# apresenta_o1.net
KiCad netlist of a schematic drawn in Altium Designer
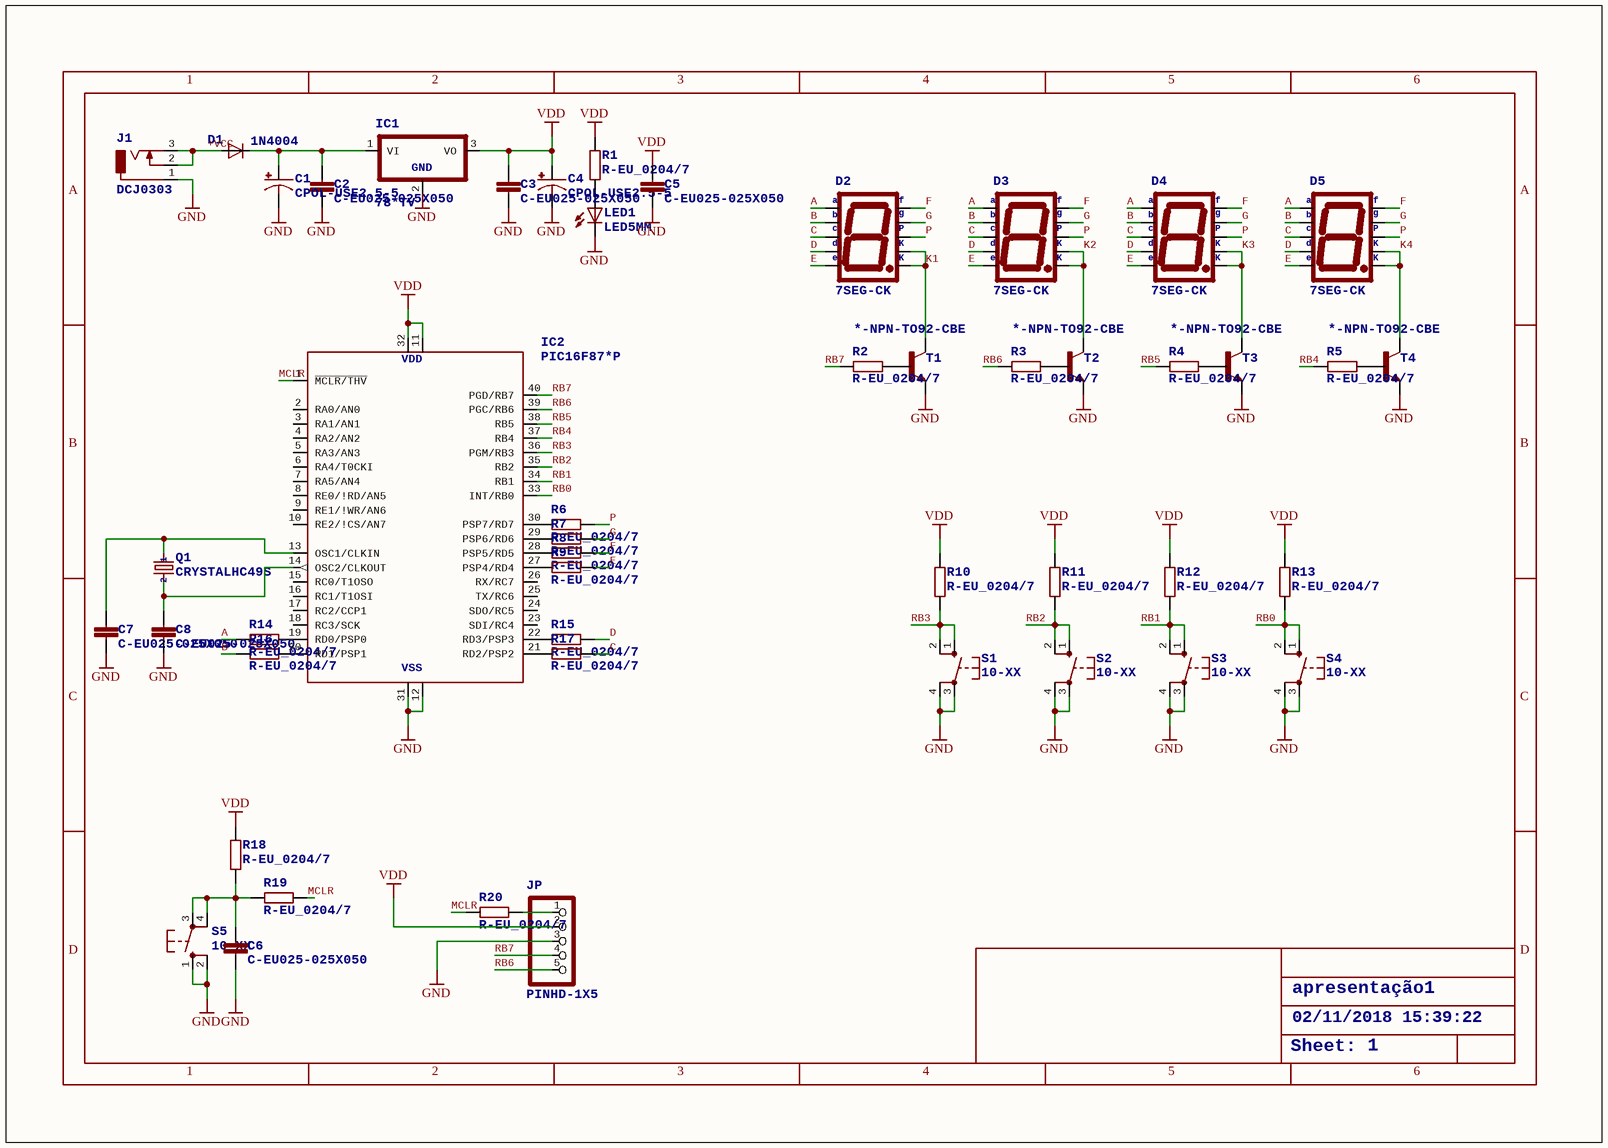
[diagram p0: apresentação1.SchDoc]

(export (version "E")
  (design (tool "Eeschema 10.0.6"))
  (components
    (comp (ref "C1")
      (value "CPOL-USE2.5-5")
      (footprint "E2,5-5")
      (description "POLARIZED CAPACITOR, American symbol")
      (libsource (lib "rcl") (part "CPOL-USE2.5-5"))
    )
    (comp (ref "C2")
      (value "C-EU025-025X050")
      (footprint "C025-025X050")
      (description "CAPACITOR, European symbol")
      (libsource (lib "rcl") (part "C-EU025-025X050"))
    )
    (comp (ref "C3")
      (value "C-EU025-025X050")
      (footprint "C025-025X050")
      (description "CAPACITOR, European symbol")
      (libsource (lib "rcl") (part "C-EU025-025X050"))
    )
    (comp (ref "C4")
      (value "CPOL-USE2.5-5")
      (footprint "E2,5-5")
      (description "POLARIZED CAPACITOR, American symbol")
      (libsource (lib "rcl") (part "CPOL-USE2.5-5"))
    )
    (comp (ref "C5")
      (value "C-EU025-025X050")
      (footprint "C025-025X050")
      (description "CAPACITOR, European symbol")
      (libsource (lib "rcl") (part "C-EU025-025X050"))
    )
    (comp (ref "C6")
      (value "C-EU025-025X050")
      (footprint "C025-025X050")
      (description "CAPACITOR, European symbol")
      (libsource (lib "rcl") (part "C-EU025-025X050"))
    )
    (comp (ref "C7")
      (value "C-EU025-025X050")
      (footprint "C025-025X050")
      (description "CAPACITOR, European symbol")
      (libsource (lib "rcl") (part "C-EU025-025X050"))
    )
    (comp (ref "C8")
      (value "C-EU025-025X050")
      (footprint "C025-025X050")
      (description "CAPACITOR, European symbol")
      (libsource (lib "rcl") (part "C-EU025-025X050"))
    )
    (comp (ref "D1")
      (value "1N4004")
      (footprint "DO41-10")
      (description "DIODE   general purpose rectifier, 1 A")
      (libsource (lib "diode") (part "1N4004"))
    )
    (comp (ref "D2")
      (value "7SEG-CK")
      (footprint "7SEG-13")
      (description "7-segment DISPLAY   single cathode, 13 mm")
      (fields
        (field (name "A") "a")
        (field (name "B") "b")
        (field (name "C") "c")
        (field (name "D") "d")
        (field (name "E") "e")
        (field (name "F") "f")
        (field (name "G") "g")
        (field (name "P") "P")
        (field (name "K") "K")
        (field (name "K_1") "K")
      )
      (libsource (lib "special") (part "7SEG-CK"))
    )
    (comp (ref "D3")
      (value "7SEG-CK")
      (footprint "7SEG-13")
      (description "7-segment DISPLAY   single cathode, 13 mm")
      (fields
        (field (name "A") "a")
        (field (name "B") "b")
        (field (name "C") "c")
        (field (name "D") "d")
        (field (name "E") "e")
        (field (name "F") "f")
        (field (name "G") "g")
        (field (name "P") "P")
        (field (name "K") "K")
        (field (name "K_1") "K")
      )
      (libsource (lib "special") (part "7SEG-CK"))
    )
    (comp (ref "D4")
      (value "7SEG-CK")
      (footprint "7SEG-13")
      (description "7-segment DISPLAY   single cathode, 13 mm")
      (fields
        (field (name "A") "a")
        (field (name "B") "b")
        (field (name "C") "c")
        (field (name "D") "d")
        (field (name "E") "e")
        (field (name "F") "f")
        (field (name "G") "g")
        (field (name "P") "P")
        (field (name "K") "K")
        (field (name "K_1") "K")
      )
      (libsource (lib "special") (part "7SEG-CK"))
    )
    (comp (ref "D5")
      (value "7SEG-CK")
      (footprint "7SEG-13")
      (description "7-segment DISPLAY   single cathode, 13 mm")
      (fields
        (field (name "A") "a")
        (field (name "B") "b")
        (field (name "C") "c")
        (field (name "D") "d")
        (field (name "E") "e")
        (field (name "F") "f")
        (field (name "G") "g")
        (field (name "P") "P")
        (field (name "K") "K")
        (field (name "K_1") "K")
      )
      (libsource (lib "special") (part "7SEG-CK"))
    )
    (comp (ref "IC1")
      (value "78*TV")
      (footprint "TO220V")
      (fields (field (name "GND") "GND"))
      (libsource (lib "linear") (part "78*TV"))
    )
    (comp (ref "IC2")
      (value "PIC16F87*P")
      (footprint "DIL40")
      (description "MICROCONTROLLER")
      (fields
        (field (name "MF") "MICROCHIP")
        (field (name "MPN") "PIC16F874-04I/P")
        (field (name "VDD") "VDD")
        (field (name "VSS") "VSS")
      )
      (libsource (lib "microchip") (part "PIC16F87*P"))
    )
    (comp (ref "J1")
      (value "DCJ0303")
      (footprint "DCJ0303")
      (description "DC POWER JACK   Source: DCJ0303.pdf")
      (libsource (lib "con-jack") (part "DCJ0303"))
    )
    (comp (ref "JP")
      (value "PINHD-1X5")
      (footprint "1X05")
      (description "PIN HEADER")
      (libsource (lib "pinhead") (part "PINHD-1X5"))
    )
    (comp (ref "LED1") (value "LED5MM") (footprint "LED5MM") (libsource (lib "led") (part "LED5MM")))
    (comp (ref "Q1")
      (value "CRYSTALHC49S")
      (footprint "HC49/S")
      (description "CRYSTAL")
      (fields (field (name "1") "1") (field (name "2") "2"))
      (libsource (lib "crystal") (part "CRYSTALHC49S"))
    )
    (comp (ref "R1")
      (value "R-EU_0204/7")
      (footprint "0204/7")
      (description "RESISTOR, European symbol")
      (libsource (lib "rcl") (part "R-EU_0204/7"))
    )
    (comp (ref "R2")
      (value "R-EU_0204/7")
      (footprint "0204/7")
      (description "RESISTOR, European symbol")
      (libsource (lib "rcl") (part "R-EU_0204/7"))
    )
    (comp (ref "R3")
      (value "R-EU_0204/7")
      (footprint "0204/7")
      (description "RESISTOR, European symbol")
      (libsource (lib "rcl") (part "R-EU_0204/7"))
    )
    (comp (ref "R4")
      (value "R-EU_0204/7")
      (footprint "0204/7")
      (description "RESISTOR, European symbol")
      (libsource (lib "rcl") (part "R-EU_0204/7"))
    )
    (comp (ref "R5")
      (value "R-EU_0204/7")
      (footprint "0204/7")
      (description "RESISTOR, European symbol")
      (libsource (lib "rcl") (part "R-EU_0204/7"))
    )
    (comp (ref "R6")
      (value "R-EU_0204/7")
      (footprint "0204/7")
      (description "RESISTOR, European symbol")
      (libsource (lib "rcl") (part "R-EU_0204/7"))
    )
    (comp (ref "R7")
      (value "R-EU_0204/7")
      (footprint "0204/7")
      (description "RESISTOR, European symbol")
      (libsource (lib "rcl") (part "R-EU_0204/7"))
    )
    (comp (ref "R8")
      (value "R-EU_0204/7")
      (footprint "0204/7")
      (description "RESISTOR, European symbol")
      (libsource (lib "rcl") (part "R-EU_0204/7"))
    )
    (comp (ref "R9")
      (value "R-EU_0204/7")
      (footprint "0204/7")
      (description "RESISTOR, European symbol")
      (libsource (lib "rcl") (part "R-EU_0204/7"))
    )
    (comp (ref "R10")
      (value "R-EU_0204/7")
      (footprint "0204/7")
      (description "RESISTOR, European symbol")
      (libsource (lib "rcl") (part "R-EU_0204/7"))
    )
    (comp (ref "R11")
      (value "R-EU_0204/7")
      (footprint "0204/7")
      (description "RESISTOR, European symbol")
      (libsource (lib "rcl") (part "R-EU_0204/7"))
    )
    (comp (ref "R12")
      (value "R-EU_0204/7")
      (footprint "0204/7")
      (description "RESISTOR, European symbol")
      (libsource (lib "rcl") (part "R-EU_0204/7"))
    )
    (comp (ref "R13")
      (value "R-EU_0204/7")
      (footprint "0204/7")
      (description "RESISTOR, European symbol")
      (libsource (lib "rcl") (part "R-EU_0204/7"))
    )
    (comp (ref "R14")
      (value "R-EU_0204/7")
      (footprint "0204/7")
      (description "RESISTOR, European symbol")
      (libsource (lib "rcl") (part "R-EU_0204/7"))
    )
    (comp (ref "R15")
      (value "R-EU_0204/7")
      (footprint "0204/7")
      (description "RESISTOR, European symbol")
      (libsource (lib "rcl") (part "R-EU_0204/7"))
    )
    (comp (ref "R16")
      (value "R-EU_0204/7")
      (footprint "0204/7")
      (description "RESISTOR, European symbol")
      (libsource (lib "rcl") (part "R-EU_0204/7"))
    )
    (comp (ref "R17")
      (value "R-EU_0204/7")
      (footprint "0204/7")
      (description "RESISTOR, European symbol")
      (libsource (lib "rcl") (part "R-EU_0204/7"))
    )
    (comp (ref "R18")
      (value "R-EU_0204/7")
      (footprint "0204/7")
      (description "RESISTOR, European symbol")
      (libsource (lib "rcl") (part "R-EU_0204/7"))
    )
    (comp (ref "R19")
      (value "R-EU_0204/7")
      (footprint "0204/7")
      (description "RESISTOR, European symbol")
      (libsource (lib "rcl") (part "R-EU_0204/7"))
    )
    (comp (ref "R20")
      (value "R-EU_0204/7")
      (footprint "0204/7")
      (description "RESISTOR, European symbol")
      (libsource (lib "rcl") (part "R-EU_0204/7"))
    )
    (comp (ref "S1")
      (value "10-XX")
      (footprint "B3F-10XX")
      (description "OMRON SWITCH")
      (fields (field (name "MPN") "B3F-1000"))
      (libsource (lib "switch-omron") (part "10-XX"))
    )
    (comp (ref "S2")
      (value "10-XX")
      (footprint "B3F-10XX")
      (description "OMRON SWITCH")
      (fields (field (name "MPN") "B3F-1000"))
      (libsource (lib "switch-omron") (part "10-XX"))
    )
    (comp (ref "S3")
      (value "10-XX")
      (footprint "B3F-10XX")
      (description "OMRON SWITCH")
      (fields (field (name "MPN") "B3F-1000"))
      (libsource (lib "switch-omron") (part "10-XX"))
    )
    (comp (ref "S4")
      (value "10-XX")
      (footprint "B3F-10XX")
      (description "OMRON SWITCH")
      (fields (field (name "MPN") "B3F-1000"))
      (libsource (lib "switch-omron") (part "10-XX"))
    )
    (comp (ref "S5")
      (value "10-XX")
      (footprint "B3F-10XX")
      (description "OMRON SWITCH")
      (fields (field (name "MPN") "B3F-1000"))
      (libsource (lib "switch-omron") (part "10-XX"))
    )
    (comp (ref "T1")
      (value "*-NPN-TO92-CBE")
      (footprint "TO92-CBE")
      (description "NPN Transistror   BF959 corrected 2008.03.06")
      (libsource (lib "transistor") (part "*-NPN-TO92-CBE"))
    )
    (comp (ref "T2")
      (value "*-NPN-TO92-CBE")
      (footprint "TO92-CBE")
      (description "NPN Transistror   BF959 corrected 2008.03.06")
      (libsource (lib "transistor") (part "*-NPN-TO92-CBE"))
    )
    (comp (ref "T3")
      (value "*-NPN-TO92-CBE")
      (footprint "TO92-CBE")
      (description "NPN Transistror   BF959 corrected 2008.03.06")
      (libsource (lib "transistor") (part "*-NPN-TO92-CBE"))
    )
    (comp (ref "T4")
      (value "*-NPN-TO92-CBE")
      (footprint "TO92-CBE")
      (description "NPN Transistror   BF959 corrected 2008.03.06")
      (libsource (lib "transistor") (part "*-NPN-TO92-CBE"))
    )
  )
  (nets
    (net (code "1") (name "/+VCC") (class "Default")
      (node (ref "D1") (pin "A") (pinfunction "A_A") (pintype "passive"))
      (node (ref "J1") (pin "2") (pinfunction "2_2") (pintype "passive"))
      (node (ref "J1") (pin "3") (pinfunction "3_3") (pintype "passive"))
    )
    (net (code "2") (name "/A") (class "Default")
      (node (ref "D2") (pin "7") (pinfunction "A_7") (pintype "passive"))
      (node (ref "D3") (pin "7") (pinfunction "A_7") (pintype "passive"))
      (node (ref "D4") (pin "7") (pinfunction "A_7") (pintype "passive"))
      (node (ref "D5") (pin "7") (pinfunction "A_7") (pintype "passive"))
      (node (ref "R14") (pin "1") (pinfunction "1_1") (pintype "passive"))
    )
    (net (code "3") (name "/B") (class "Default")
      (node (ref "D2") (pin "6") (pinfunction "B_6") (pintype "passive"))
      (node (ref "D3") (pin "6") (pinfunction "B_6") (pintype "passive"))
      (node (ref "D4") (pin "6") (pinfunction "B_6") (pintype "passive"))
      (node (ref "D5") (pin "6") (pinfunction "B_6") (pintype "passive"))
      (node (ref "R16") (pin "1") (pinfunction "1_1") (pintype "passive"))
    )
    (net (code "4") (name "/C") (class "Default")
      (node (ref "D2") (pin "4") (pinfunction "C_4") (pintype "passive"))
      (node (ref "D3") (pin "4") (pinfunction "C_4") (pintype "passive"))
      (node (ref "D4") (pin "4") (pinfunction "C_4") (pintype "passive"))
      (node (ref "D5") (pin "4") (pinfunction "C_4") (pintype "passive"))
      (node (ref "R17") (pin "2") (pinfunction "2_2") (pintype "passive"))
    )
    (net (code "5") (name "/D") (class "Default")
      (node (ref "D2") (pin "2") (pinfunction "D_2") (pintype "passive"))
      (node (ref "D3") (pin "2") (pinfunction "D_2") (pintype "passive"))
      (node (ref "D4") (pin "2") (pinfunction "D_2") (pintype "passive"))
      (node (ref "D5") (pin "2") (pinfunction "D_2") (pintype "passive"))
      (node (ref "R15") (pin "2") (pinfunction "2_2") (pintype "passive"))
    )
    (net (code "6") (name "/E") (class "Default")
      (node (ref "D2") (pin "1") (pinfunction "E_1") (pintype "passive"))
      (node (ref "D3") (pin "1") (pinfunction "E_1") (pintype "passive"))
      (node (ref "D4") (pin "1") (pinfunction "E_1") (pintype "passive"))
      (node (ref "D5") (pin "1") (pinfunction "E_1") (pintype "passive"))
      (node (ref "R9") (pin "2") (pinfunction "2_2") (pintype "passive"))
    )
    (net (code "7") (name "/F") (class "Default")
      (node (ref "D2") (pin "9") (pinfunction "F_9") (pintype "passive"))
      (node (ref "D3") (pin "9") (pinfunction "F_9") (pintype "passive"))
      (node (ref "D4") (pin "9") (pinfunction "F_9") (pintype "passive"))
      (node (ref "D5") (pin "9") (pinfunction "F_9") (pintype "passive"))
      (node (ref "R8") (pin "2") (pinfunction "2_2") (pintype "passive"))
    )
    (net (code "8") (name "/G") (class "Default")
      (node (ref "D2") (pin "10") (pinfunction "G_10") (pintype "passive"))
      (node (ref "D3") (pin "10") (pinfunction "G_10") (pintype "passive"))
      (node (ref "D4") (pin "10") (pinfunction "G_10") (pintype "passive"))
      (node (ref "D5") (pin "10") (pinfunction "G_10") (pintype "passive"))
      (node (ref "R7") (pin "2") (pinfunction "2_2") (pintype "passive"))
    )
    (net (code "9") (name "/K1") (class "Default")
      (node (ref "D2") (pin "3") (pinfunction "CK1_3") (pintype "passive"))
      (node (ref "D2") (pin "8") (pinfunction "CK2_8") (pintype "passive"))
      (node (ref "T1") (pin "C") (pinfunction "C_C") (pintype "passive"))
    )
    (net (code "10") (name "/K2") (class "Default")
      (node (ref "D3") (pin "3") (pinfunction "CK1_3") (pintype "passive"))
      (node (ref "D3") (pin "8") (pinfunction "CK2_8") (pintype "passive"))
      (node (ref "T2") (pin "C") (pinfunction "C_C") (pintype "passive"))
    )
    (net (code "11") (name "/K3") (class "Default")
      (node (ref "D4") (pin "3") (pinfunction "CK1_3") (pintype "passive"))
      (node (ref "D4") (pin "8") (pinfunction "CK2_8") (pintype "passive"))
      (node (ref "T3") (pin "C") (pinfunction "C_C") (pintype "passive"))
    )
    (net (code "12") (name "/K4") (class "Default")
      (node (ref "D5") (pin "3") (pinfunction "CK1_3") (pintype "passive"))
      (node (ref "D5") (pin "8") (pinfunction "CK2_8") (pintype "passive"))
      (node (ref "T4") (pin "C") (pinfunction "C_C") (pintype "passive"))
    )
    (net (code "13") (name "/MCLR") (class "Default")
      (node (ref "IC2") (pin "1") (pinfunction "~{MCLR/THV}_1") (pintype "passive"))
      (node (ref "R19") (pin "1") (pinfunction "1_1") (pintype "passive"))
      (node (ref "R20") (pin "2") (pinfunction "2_2") (pintype "passive"))
    )
    (net (code "14") (name "/P") (class "Default")
      (node (ref "D2") (pin "5") (pinfunction "DP_5") (pintype "passive"))
      (node (ref "D3") (pin "5") (pinfunction "DP_5") (pintype "passive"))
      (node (ref "D4") (pin "5") (pinfunction "DP_5") (pintype "passive"))
      (node (ref "D5") (pin "5") (pinfunction "DP_5") (pintype "passive"))
      (node (ref "R6") (pin "2") (pinfunction "2_2") (pintype "passive"))
    )
    (net (code "15") (name "/RB0") (class "Default")
      (node (ref "IC2") (pin "33") (pinfunction "INT/RB0_33") (pintype "passive"))
      (node (ref "R13") (pin "1") (pinfunction "1_1") (pintype "passive"))
      (node (ref "S4") (pin "1") (pinfunction "S_1") (pintype "passive"))
      (node (ref "S4") (pin "2") (pinfunction "S1_2") (pintype "passive"))
    )
    (net (code "16") (name "/RB1") (class "Default")
      (node (ref "IC2") (pin "34") (pinfunction "RB1_34") (pintype "passive"))
      (node (ref "R12") (pin "1") (pinfunction "1_1") (pintype "passive"))
      (node (ref "S3") (pin "1") (pinfunction "S_1") (pintype "passive"))
      (node (ref "S3") (pin "2") (pinfunction "S1_2") (pintype "passive"))
    )
    (net (code "17") (name "/RB2") (class "Default")
      (node (ref "IC2") (pin "35") (pinfunction "RB2_35") (pintype "passive"))
      (node (ref "R11") (pin "1") (pinfunction "1_1") (pintype "passive"))
      (node (ref "S2") (pin "1") (pinfunction "S_1") (pintype "passive"))
      (node (ref "S2") (pin "2") (pinfunction "S1_2") (pintype "passive"))
    )
    (net (code "18") (name "/RB3") (class "Default")
      (node (ref "IC2") (pin "36") (pinfunction "PGM/RB3_36") (pintype "passive"))
      (node (ref "R10") (pin "1") (pinfunction "1_1") (pintype "passive"))
      (node (ref "S1") (pin "1") (pinfunction "S_1") (pintype "passive"))
      (node (ref "S1") (pin "2") (pinfunction "S1_2") (pintype "passive"))
    )
    (net (code "19") (name "/RB4") (class "Default")
      (node (ref "IC2") (pin "37") (pinfunction "RB4_37") (pintype "passive"))
      (node (ref "R5") (pin "1") (pinfunction "1_1") (pintype "passive"))
    )
    (net (code "20") (name "/RB5") (class "Default")
      (node (ref "IC2") (pin "38") (pinfunction "RB5_38") (pintype "passive"))
      (node (ref "R4") (pin "1") (pinfunction "1_1") (pintype "passive"))
    )
    (net (code "21") (name "/RB6") (class "Default")
      (node (ref "IC2") (pin "39") (pinfunction "PGC/RB6_39") (pintype "passive"))
      (node (ref "JP") (pin "5") (pinfunction "5_5") (pintype "passive"))
      (node (ref "R3") (pin "1") (pinfunction "1_1") (pintype "passive"))
    )
    (net (code "22") (name "/RB7") (class "Default")
      (node (ref "IC2") (pin "40") (pinfunction "PGD/RB7_40") (pintype "passive"))
      (node (ref "JP") (pin "4") (pinfunction "4_4") (pintype "passive"))
      (node (ref "R2") (pin "1") (pinfunction "1_1") (pintype "passive"))
    )
    (net (code "23") (name "GND") (class "Default")
      (node (ref "C1") (pin "-") (pinfunction "-_-") (pintype "passive"))
      (node (ref "C2") (pin "2") (pinfunction "2_2") (pintype "passive"))
      (node (ref "C3") (pin "2") (pinfunction "2_2") (pintype "passive"))
      (node (ref "C4") (pin "-") (pinfunction "-_-") (pintype "passive"))
      (node (ref "C5") (pin "2") (pinfunction "2_2") (pintype "passive"))
      (node (ref "C6") (pin "2") (pinfunction "2_2") (pintype "passive"))
      (node (ref "C7") (pin "2") (pinfunction "2_2") (pintype "passive"))
      (node (ref "C8") (pin "2") (pinfunction "2_2") (pintype "passive"))
      (node (ref "IC1") (pin "2") (pinfunction "GND_2") (pintype "passive"))
      (node (ref "IC2") (pin "12") (pinfunction "VSS_12") (pintype "power_in"))
      (node (ref "IC2") (pin "31") (pinfunction "VSS_31") (pintype "power_in"))
      (node (ref "J1") (pin "1") (pinfunction "1_1") (pintype "passive"))
      (node (ref "JP") (pin "3") (pinfunction "3_3") (pintype "passive"))
      (node (ref "LED1") (pin "K") (pinfunction "C_K") (pintype "passive"))
      (node (ref "S1") (pin "3") (pinfunction "P_3") (pintype "passive"))
      (node (ref "S1") (pin "4") (pinfunction "P1_4") (pintype "passive"))
      (node (ref "S2") (pin "3") (pinfunction "P_3") (pintype "passive"))
      (node (ref "S2") (pin "4") (pinfunction "P1_4") (pintype "passive"))
      (node (ref "S3") (pin "3") (pinfunction "P_3") (pintype "passive"))
      (node (ref "S3") (pin "4") (pinfunction "P1_4") (pintype "passive"))
      (node (ref "S4") (pin "3") (pinfunction "P_3") (pintype "passive"))
      (node (ref "S4") (pin "4") (pinfunction "P1_4") (pintype "passive"))
      (node (ref "S5") (pin "1") (pinfunction "S_1") (pintype "passive"))
      (node (ref "S5") (pin "2") (pinfunction "S1_2") (pintype "passive"))
      (node (ref "T1") (pin "E") (pinfunction "E_E") (pintype "passive"))
      (node (ref "T2") (pin "E") (pinfunction "E_E") (pintype "passive"))
      (node (ref "T3") (pin "E") (pinfunction "E_E") (pintype "passive"))
      (node (ref "T4") (pin "E") (pinfunction "E_E") (pintype "passive"))
    )
    (net (code "24") (name "Net-(IC1-VI)") (class "Default")
      (node (ref "C1") (pin "+") (pinfunction "+_+") (pintype "passive"))
      (node (ref "C2") (pin "1") (pinfunction "1_1") (pintype "passive"))
      (node (ref "D1") (pin "C") (pinfunction "C_C") (pintype "passive"))
      (node (ref "IC1") (pin "1") (pinfunction "VI_1") (pintype "passive"))
    )
    (net (code "25") (name "Net-(IC2-OSC1{slash}CLKIN)") (class "Default")
      (node (ref "C7") (pin "1") (pinfunction "1_1") (pintype "passive"))
      (node (ref "IC2") (pin "13") (pinfunction "OSC1/CLKIN_13") (pintype "passive"))
      (node (ref "Q1") (pin "1") (pinfunction "1_1") (pintype "passive"))
    )
    (net (code "26") (name "Net-(IC2-OSC2{slash}CLKOUT)") (class "Default")
      (node (ref "C8") (pin "1") (pinfunction "1_1") (pintype "passive"))
      (node (ref "IC2") (pin "14") (pinfunction "OSC2/CLKOUT_14") (pintype "output"))
      (node (ref "Q1") (pin "2") (pinfunction "2_2") (pintype "passive"))
    )
    (net (code "27") (name "Net-(IC2-PSP4{slash}RD4)") (class "Default")
      (node (ref "IC2") (pin "27") (pinfunction "PSP4/RD4_27") (pintype "passive"))
      (node (ref "R9") (pin "1") (pinfunction "1_1") (pintype "passive"))
    )
    (net (code "28") (name "Net-(IC2-PSP5{slash}RD5)") (class "Default")
      (node (ref "IC2") (pin "28") (pinfunction "PSP5/RD5_28") (pintype "passive"))
      (node (ref "R8") (pin "1") (pinfunction "1_1") (pintype "passive"))
    )
    (net (code "29") (name "Net-(IC2-PSP6{slash}RD6)") (class "Default")
      (node (ref "IC2") (pin "29") (pinfunction "PSP6/RD6_29") (pintype "passive"))
      (node (ref "R7") (pin "1") (pinfunction "1_1") (pintype "passive"))
    )
    (net (code "30") (name "Net-(IC2-PSP7{slash}RD7)") (class "Default")
      (node (ref "IC2") (pin "30") (pinfunction "PSP7/RD7_30") (pintype "passive"))
      (node (ref "R6") (pin "1") (pinfunction "1_1") (pintype "passive"))
    )
    (net (code "31") (name "Net-(IC2-RD0{slash}PSP0)") (class "Default")
      (node (ref "IC2") (pin "19") (pinfunction "RD0/PSP0_19") (pintype "passive"))
      (node (ref "R14") (pin "2") (pinfunction "2_2") (pintype "passive"))
    )
    (net (code "32") (name "Net-(IC2-RD1{slash}PSP1)") (class "Default")
      (node (ref "IC2") (pin "20") (pinfunction "RD1/PSP1_20") (pintype "passive"))
      (node (ref "R16") (pin "2") (pinfunction "2_2") (pintype "passive"))
    )
    (net (code "33") (name "Net-(IC2-RD2{slash}PSP2)") (class "Default")
      (node (ref "IC2") (pin "21") (pinfunction "RD2/PSP2_21") (pintype "passive"))
      (node (ref "R17") (pin "1") (pinfunction "1_1") (pintype "passive"))
    )
    (net (code "34") (name "Net-(IC2-RD3{slash}PSP3)") (class "Default")
      (node (ref "IC2") (pin "22") (pinfunction "RD3/PSP3_22") (pintype "passive"))
      (node (ref "R15") (pin "1") (pinfunction "1_1") (pintype "passive"))
    )
    (net (code "35") (name "Net-(JP-Pad1)") (class "Default")
      (node (ref "JP") (pin "1") (pinfunction "1_1") (pintype "passive"))
      (node (ref "R20") (pin "1") (pinfunction "1_1") (pintype "passive"))
    )
    (net (code "36") (name "Net-(LED1-PadA)") (class "Default")
      (node (ref "LED1") (pin "A") (pinfunction "A_A") (pintype "passive"))
      (node (ref "R1") (pin "2") (pinfunction "2_2") (pintype "passive"))
    )
    (net (code "37") (name "Net-(R2-Pad2)") (class "Default")
      (node (ref "R2") (pin "2") (pinfunction "2_2") (pintype "passive"))
      (node (ref "T1") (pin "B") (pinfunction "B_B") (pintype "passive"))
    )
    (net (code "38") (name "Net-(R3-Pad2)") (class "Default")
      (node (ref "R3") (pin "2") (pinfunction "2_2") (pintype "passive"))
      (node (ref "T2") (pin "B") (pinfunction "B_B") (pintype "passive"))
    )
    (net (code "39") (name "Net-(R4-Pad2)") (class "Default")
      (node (ref "R4") (pin "2") (pinfunction "2_2") (pintype "passive"))
      (node (ref "T3") (pin "B") (pinfunction "B_B") (pintype "passive"))
    )
    (net (code "40") (name "Net-(R5-Pad2)") (class "Default")
      (node (ref "R5") (pin "2") (pinfunction "2_2") (pintype "passive"))
      (node (ref "T4") (pin "B") (pinfunction "B_B") (pintype "passive"))
    )
    (net (code "41") (name "Net-(S5-P)") (class "Default")
      (node (ref "C6") (pin "1") (pinfunction "1_1") (pintype "passive"))
      (node (ref "R18") (pin "1") (pinfunction "1_1") (pintype "passive"))
      (node (ref "R19") (pin "2") (pinfunction "2_2") (pintype "passive"))
      (node (ref "S5") (pin "3") (pinfunction "P_3") (pintype "passive"))
      (node (ref "S5") (pin "4") (pinfunction "P1_4") (pintype "passive"))
    )
    (net (code "42") (name "VDD") (class "Default")
      (node (ref "C3") (pin "1") (pinfunction "1_1") (pintype "passive"))
      (node (ref "C4") (pin "+") (pinfunction "+_+") (pintype "passive"))
      (node (ref "C5") (pin "1") (pinfunction "1_1") (pintype "passive"))
      (node (ref "IC1") (pin "3") (pinfunction "VO_3") (pintype "passive"))
      (node (ref "IC2") (pin "11") (pinfunction "VDD_11") (pintype "power_in"))
      (node (ref "IC2") (pin "32") (pinfunction "VDD_32") (pintype "power_in"))
      (node (ref "JP") (pin "2") (pinfunction "2_2") (pintype "passive"))
      (node (ref "R1") (pin "1") (pinfunction "1_1") (pintype "passive"))
      (node (ref "R10") (pin "2") (pinfunction "2_2") (pintype "passive"))
      (node (ref "R11") (pin "2") (pinfunction "2_2") (pintype "passive"))
      (node (ref "R12") (pin "2") (pinfunction "2_2") (pintype "passive"))
      (node (ref "R13") (pin "2") (pinfunction "2_2") (pintype "passive"))
      (node (ref "R18") (pin "2") (pinfunction "2_2") (pintype "passive"))
    )
    (net (code "43") (name "unconnected-(IC2-RA0{slash}AN0-Pad2)") (class "Default")
      (node (ref "IC2") (pin "2") (pinfunction "RA0/AN0_2") (pintype "passive"))
    )
    (net (code "44") (name "unconnected-(IC2-RA1{slash}AN1-Pad3)") (class "Default")
      (node (ref "IC2") (pin "3") (pinfunction "RA1/AN1_3") (pintype "passive"))
    )
    (net (code "45") (name "unconnected-(IC2-RA2{slash}AN2-Pad4)") (class "Default")
      (node (ref "IC2") (pin "4") (pinfunction "RA2/AN2_4") (pintype "passive"))
    )
    (net (code "46") (name "unconnected-(IC2-RA3{slash}AN3-Pad5)") (class "Default")
      (node (ref "IC2") (pin "5") (pinfunction "RA3/AN3_5") (pintype "passive"))
    )
    (net (code "47") (name "unconnected-(IC2-RA4{slash}T0CKI-Pad6)") (class "Default")
      (node (ref "IC2") (pin "6") (pinfunction "RA4/T0CKI_6") (pintype "passive"))
    )
    (net (code "48") (name "unconnected-(IC2-RA5{slash}AN4-Pad7)") (class "Default")
      (node (ref "IC2") (pin "7") (pinfunction "RA5/AN4_7") (pintype "passive"))
    )
    (net (code "49") (name "unconnected-(IC2-RC0{slash}T1OSO-Pad15)") (class "Default")
      (node (ref "IC2") (pin "15") (pinfunction "RC0/T1OSO_15") (pintype "passive"))
    )
    (net (code "50") (name "unconnected-(IC2-RC1{slash}T1OSI-Pad16)") (class "Default")
      (node (ref "IC2") (pin "16") (pinfunction "RC1/T1OSI_16") (pintype "passive"))
    )
    (net (code "51") (name "unconnected-(IC2-RC2{slash}CCP1-Pad17)") (class "Default")
      (node (ref "IC2") (pin "17") (pinfunction "RC2/CCP1_17") (pintype "passive"))
    )
    (net (code "52") (name "unconnected-(IC2-RC3{slash}SCK-Pad18)") (class "Default")
      (node (ref "IC2") (pin "18") (pinfunction "RC3/SCK_18") (pintype "passive"))
    )
    (net (code "53") (name "unconnected-(IC2-RE0{slash}!RD{slash}AN5-Pad8)") (class "Default")
      (node (ref "IC2") (pin "8") (pinfunction "RE0/!RD/AN5_8") (pintype "passive"))
    )
    (net (code "54") (name "unconnected-(IC2-RE1{slash}!WR{slash}AN6-Pad9)") (class "Default")
      (node (ref "IC2") (pin "9") (pinfunction "RE1/!WR/AN6_9") (pintype "passive"))
    )
    (net (code "55") (name "unconnected-(IC2-RE2{slash}!CS{slash}AN7-Pad10)") (class "Default")
      (node (ref "IC2") (pin "10") (pinfunction "RE2/!CS/AN7_10") (pintype "passive"))
    )
    (net (code "56") (name "unconnected-(IC2-RX{slash}RC7-Pad26)") (class "Default")
      (node (ref "IC2") (pin "26") (pinfunction "RX/RC7_26") (pintype "passive"))
    )
    (net (code "57") (name "unconnected-(IC2-SDI{slash}RC4-Pad23)") (class "Default")
      (node (ref "IC2") (pin "23") (pinfunction "SDI/RC4_23") (pintype "passive"))
    )
    (net (code "58") (name "unconnected-(IC2-SDO{slash}RC5-Pad24)") (class "Default")
      (node (ref "IC2") (pin "24") (pinfunction "SDO/RC5_24") (pintype "passive"))
    )
    (net (code "59") (name "unconnected-(IC2-TX{slash}RC6-Pad25)") (class "Default")
      (node (ref "IC2") (pin "25") (pinfunction "TX/RC6_25") (pintype "passive"))
    )
  )
)
